# lcamp.net
KiCad netlist of a schematic drawn in EAGLE
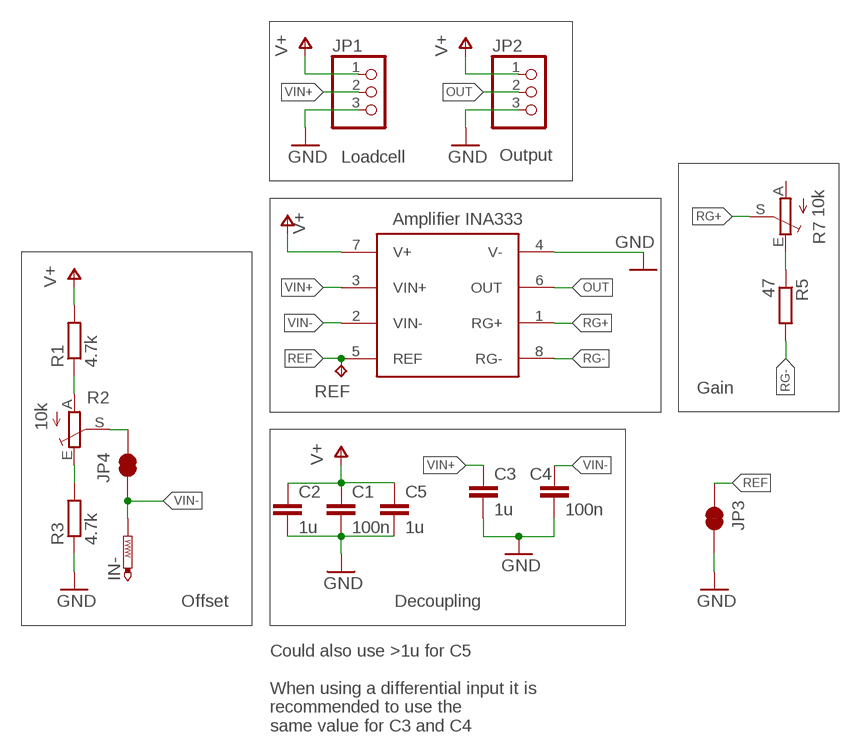
[diagram p0: schematic, sheet 1]

(export (version "E")
  (design (tool "Eeschema 10.0.6"))
  (components
    (comp (ref "C1")
      (value "100n")
      (footprint "eagle-import:C0603")
      (libsource (lib "eagle-import") (part "C-EUC0603"))
    )
    (comp (ref "C2")
      (value "1u")
      (footprint "eagle-import:C0603")
      (libsource (lib "eagle-import") (part "C-EUC0603"))
    )
    (comp (ref "C3")
      (value "1u")
      (footprint "eagle-import:C0603")
      (libsource (lib "eagle-import") (part "C-EUC0603"))
    )
    (comp (ref "C4")
      (value "100n")
      (footprint "eagle-import:C0603")
      (libsource (lib "eagle-import") (part "C-EUC0603"))
    )
    (comp (ref "C5")
      (value "1u")
      (footprint "eagle-import:C0603")
      (libsource (lib "eagle-import") (part "C-EUC0603"))
    )
    (comp (ref "IN-")
      (value "PTR1PAD1-13")
      (footprint "eagle-import:P1-13")
      (libsource (lib "eagle-import") (part "PTR1PAD1-13"))
    )
    (comp (ref "JP1")
      (value "PINHD-1X3")
      (footprint "eagle-import:1X03")
      (libsource (lib "eagle-import") (part "PINHD-1X3"))
    )
    (comp (ref "JP2")
      (value "PINHD-1X3")
      (footprint "eagle-import:1X03")
      (libsource (lib "eagle-import") (part "PINHD-1X3"))
    )
    (comp (ref "JP3")
      (value "JUMPER-SMT_2_NC_TRACE_SILK")
      (footprint "eagle-import:SMT-JUMPER_2_NC_TRACE_SILK")
      (libsource (lib "eagle-import") (part "JUMPER-SMT_2_NC_TRACE_SILK"))
    )
    (comp (ref "JP4")
      (value "JUMPER-SMT_2_NC_TRACE_SILK")
      (footprint "eagle-import:SMT-JUMPER_2_NC_TRACE_SILK")
      (libsource (lib "eagle-import") (part "JUMPER-SMT_2_NC_TRACE_SILK"))
    )
    (comp (ref "R1")
      (value "4.7k")
      (footprint "eagle-import:R0603")
      (libsource (lib "eagle-import") (part "R-EU_R0603"))
    )
    (comp (ref "R2")
      (value "10k")
      (footprint "eagle-import:RJ9W")
      (libsource (lib "eagle-import") (part "TRIM_EU-RJ9W"))
    )
    (comp (ref "R3")
      (value "4.7k")
      (footprint "eagle-import:R0603")
      (libsource (lib "eagle-import") (part "R-EU_R0603"))
    )
    (comp (ref "R5")
      (value "47")
      (footprint "eagle-import:R0603")
      (libsource (lib "eagle-import") (part "R-EU_R0603"))
    )
    (comp (ref "R7")
      (value "10k")
      (footprint "eagle-import:RJ9W")
      (libsource (lib "eagle-import") (part "TRIM_EU-RJ9W"))
    )
    (comp (ref "REF")
      (value "TPB1,27")
      (footprint "eagle-import:B1,27")
      (libsource (lib "eagle-import") (part "TPB1,27"))
    )
    (comp (ref "U1")
      (value "INA333MSOP8")
      (footprint "eagle-import:MSOP8")
      (libsource (lib "eagle-import") (part "INA333MSOP8"))
    )
  )
  (nets
    (net (code "1") (name "GND") (class "Default")
      (node (ref "C1") (pin "2") (pinfunction "2_2") (pintype "passive"))
      (node (ref "C2") (pin "2") (pinfunction "2_2") (pintype "passive"))
      (node (ref "C3") (pin "2") (pinfunction "2_2") (pintype "passive"))
      (node (ref "C4") (pin "2") (pinfunction "2_2") (pintype "passive"))
      (node (ref "C5") (pin "2") (pinfunction "2_2") (pintype "passive"))
      (node (ref "JP1") (pin "3") (pinfunction "3_3") (pintype "passive"))
      (node (ref "JP2") (pin "3") (pinfunction "3_3") (pintype "passive"))
      (node (ref "JP3") (pin "2") (pinfunction "2_2") (pintype "passive"))
      (node (ref "R3") (pin "1") (pinfunction "1_1") (pintype "passive"))
      (node (ref "U1") (pin "4") (pinfunction "V-_4") (pintype "bidirectional"))
    )
    (net (code "2") (name "Net-(JP4-Pad2)") (class "Default")
      (node (ref "JP4") (pin "2") (pinfunction "2_2") (pintype "passive"))
      (node (ref "R2") (pin "S") (pinfunction "S_S") (pintype "passive"))
    )
    (net (code "3") (name "Net-(R1-Pad1)") (class "Default")
      (node (ref "R1") (pin "1") (pinfunction "1_1") (pintype "passive"))
      (node (ref "R2") (pin "A") (pinfunction "A_A") (pintype "passive"))
    )
    (net (code "4") (name "Net-(R2-PadE)") (class "Default")
      (node (ref "R2") (pin "E") (pinfunction "E_E") (pintype "passive"))
      (node (ref "R3") (pin "2") (pinfunction "2_2") (pintype "passive"))
    )
    (net (code "5") (name "Net-(R5-Pad1)") (class "Default")
      (node (ref "R5") (pin "1") (pinfunction "1_1") (pintype "passive"))
      (node (ref "R7") (pin "E") (pinfunction "E_E") (pintype "passive"))
    )
    (net (code "6") (name "OUT") (class "Default")
      (node (ref "JP2") (pin "2") (pinfunction "2_2") (pintype "passive"))
      (node (ref "U1") (pin "6") (pinfunction "OUT_6") (pintype "bidirectional"))
    )
    (net (code "7") (name "REF") (class "Default")
      (node (ref "JP3") (pin "1") (pinfunction "1_1") (pintype "passive"))
      (node (ref "REF") (pin "TP") (pinfunction "TP_TP") (pintype "input"))
      (node (ref "U1") (pin "5") (pinfunction "REF_5") (pintype "bidirectional"))
    )
    (net (code "8") (name "RG+") (class "Default")
      (node (ref "R7") (pin "S") (pinfunction "S_S") (pintype "passive"))
      (node (ref "U1") (pin "1") (pinfunction "RG+_1") (pintype "bidirectional"))
    )
    (net (code "9") (name "RG-") (class "Default")
      (node (ref "R5") (pin "2") (pinfunction "2_2") (pintype "passive"))
      (node (ref "U1") (pin "8") (pinfunction "RG-_8") (pintype "bidirectional"))
    )
    (net (code "10") (name "V+") (class "Default")
      (node (ref "C1") (pin "1") (pinfunction "1_1") (pintype "passive"))
      (node (ref "C2") (pin "1") (pinfunction "1_1") (pintype "passive"))
      (node (ref "C5") (pin "1") (pinfunction "1_1") (pintype "passive"))
      (node (ref "JP1") (pin "1") (pinfunction "1_1") (pintype "passive"))
      (node (ref "JP2") (pin "1") (pinfunction "1_1") (pintype "passive"))
      (node (ref "R1") (pin "2") (pinfunction "2_2") (pintype "passive"))
      (node (ref "U1") (pin "7") (pinfunction "V+_7") (pintype "bidirectional"))
    )
    (net (code "11") (name "VIN+") (class "Default")
      (node (ref "C3") (pin "1") (pinfunction "1_1") (pintype "passive"))
      (node (ref "JP1") (pin "2") (pinfunction "2_2") (pintype "passive"))
      (node (ref "U1") (pin "3") (pinfunction "VIN+_3") (pintype "bidirectional"))
    )
    (net (code "12") (name "VIN-") (class "Default")
      (node (ref "C4") (pin "1") (pinfunction "1_1") (pintype "passive"))
      (node (ref "IN-") (pin "TP") (pinfunction "TP_TP") (pintype "input"))
      (node (ref "JP4") (pin "1") (pinfunction "1_1") (pintype "passive"))
      (node (ref "U1") (pin "2") (pinfunction "VIN-_2") (pintype "bidirectional"))
    )
    (net (code "13") (name "unconnected-(R7-PadA)") (class "Default")
      (node (ref "R7") (pin "A") (pinfunction "A_A") (pintype "passive"))
    )
  )
)
